# EncoderPCB_V1_0.net
KiCad netlist of a schematic drawn in EAGLE
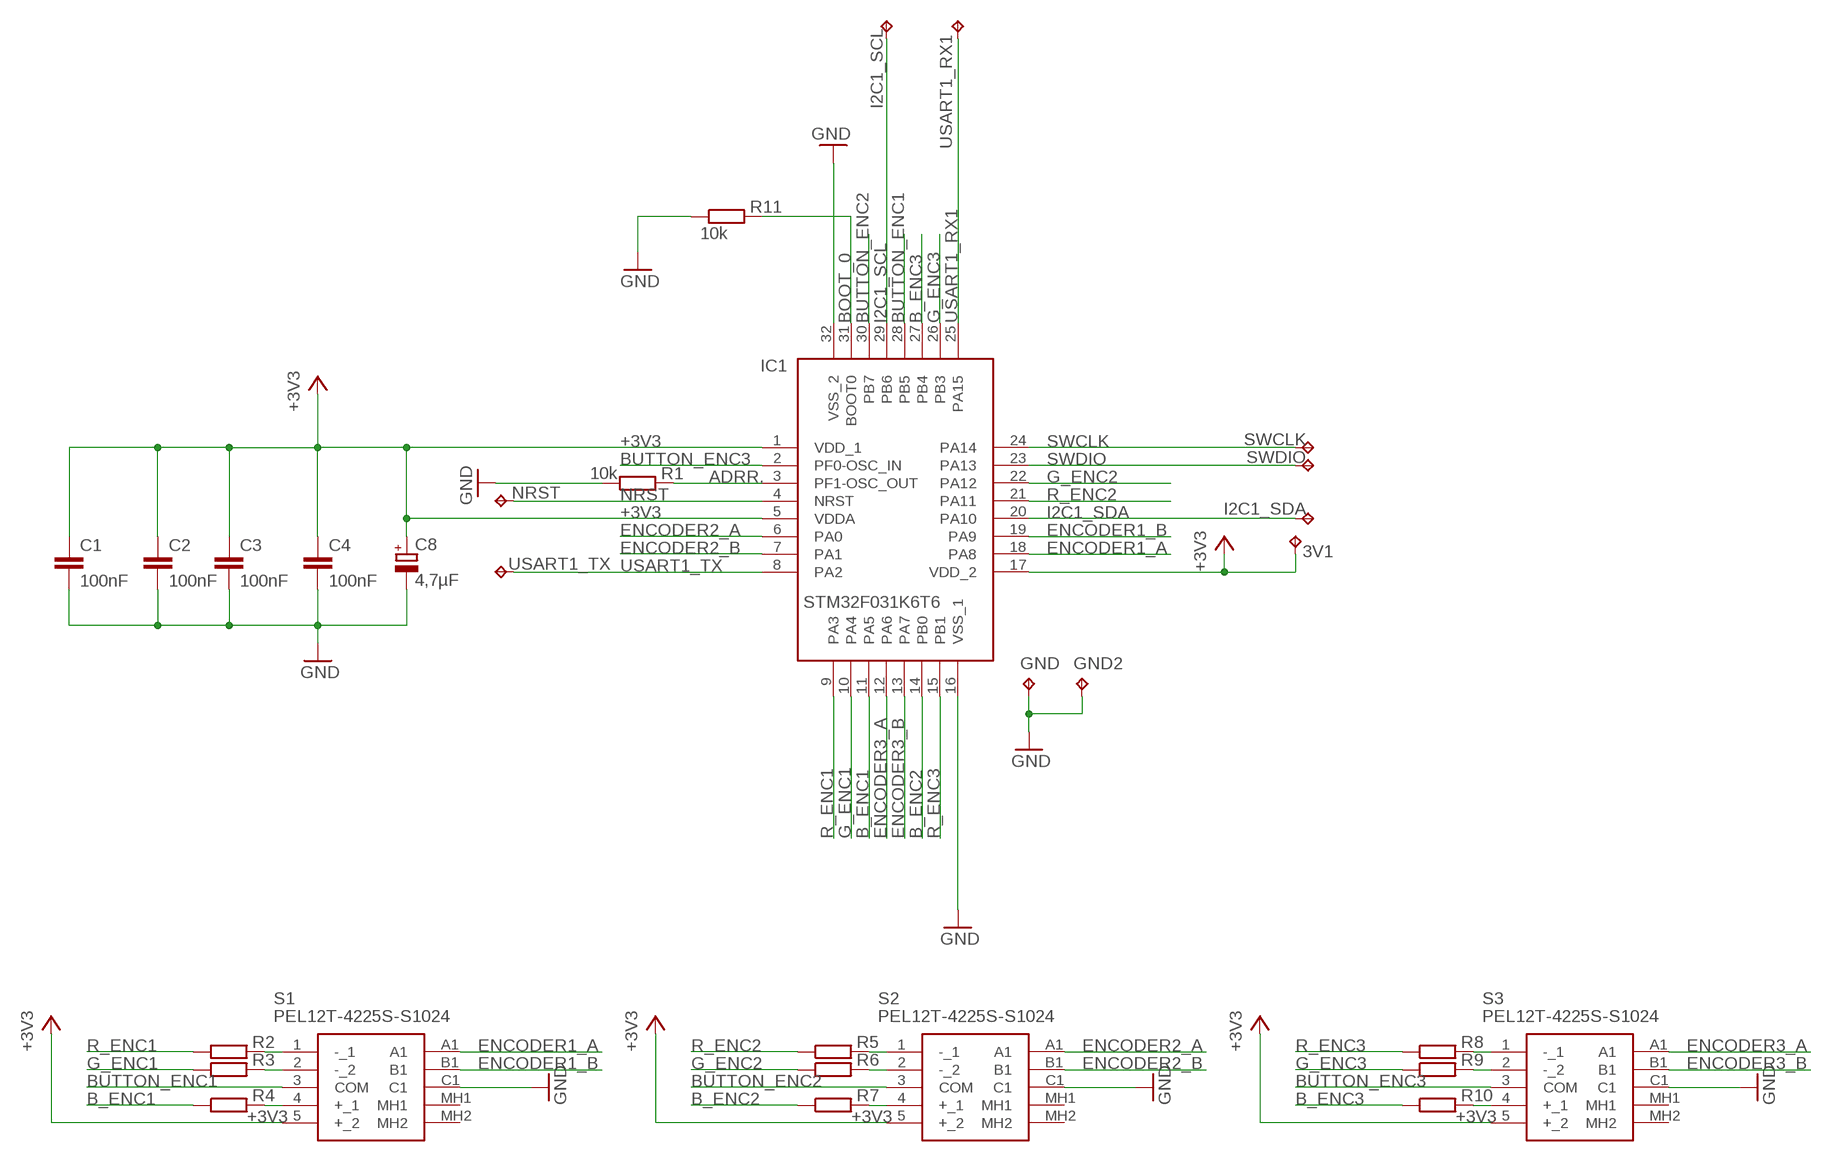
[diagram p0: schematic, sheet 1]

(export (version "E")
  (design (tool "Eeschema 10.0.6"))
  (components
    (comp (ref "3V1")
      (value "TPTHT")
      (footprint "eagle-import:THT_PIN")
      (libsource (lib "eagle-import") (part "TPTHT"))
    )
    (comp (ref "C1")
      (value "100nF")
      (footprint "eagle-import:C0603")
      (libsource (lib "eagle-import") (part "CAPACITOR{dblquote}"))
    )
    (comp (ref "C2")
      (value "100nF")
      (footprint "eagle-import:C0603")
      (libsource (lib "eagle-import") (part "CAPACITOR{dblquote}"))
    )
    (comp (ref "C3")
      (value "100nF")
      (footprint "eagle-import:C0603")
      (libsource (lib "eagle-import") (part "CAPACITOR{dblquote}"))
    )
    (comp (ref "C4")
      (value "100nF")
      (footprint "eagle-import:C0603")
      (libsource (lib "eagle-import") (part "CAPACITOR{dblquote}"))
    )
    (comp (ref "C8")
      (value "4,7µF")
      (footprint "eagle-import:153CLV-0605")
      (libsource (lib "eagle-import") (part "SMD_ELCTROLYTIC"))
    )
    (comp (ref "GND")
      (value "TPTHT")
      (footprint "eagle-import:THT_PIN")
      (libsource (lib "eagle-import") (part "TPTHT"))
    )
    (comp (ref "GND2")
      (value "TPTHT")
      (footprint "eagle-import:THT_PIN")
      (libsource (lib "eagle-import") (part "TPTHT"))
    )
    (comp (ref "I2C1_SCL")
      (value "TPTHT")
      (footprint "eagle-import:THT_PIN")
      (libsource (lib "eagle-import") (part "TPTHT"))
    )
    (comp (ref "I2C1_SDA")
      (value "TPTHT")
      (footprint "eagle-import:THT_PIN")
      (libsource (lib "eagle-import") (part "TPTHT"))
    )
    (comp (ref "IC1")
      (value "STM32F031K6T6")
      (footprint "eagle-import:QFP80P900X900X160-32N")
      (fields (field (name "MOUSER_PART_NUMBER") "511-STM32F031K6T6"))
      (libsource (lib "eagle-import") (part "STM32F031K6T6"))
    )
    (comp (ref "NRST")
      (value "TPTHT")
      (footprint "eagle-import:THT_PIN")
      (libsource (lib "eagle-import") (part "TPTHT"))
    )
    (comp (ref "R1")
      (value "10k")
      (footprint "eagle-import:R0805")
      (libsource (lib "eagle-import") (part "RESISTOR{dblquote}"))
    )
    (comp (ref "R2")
      (value "RESISTOR\"")
      (footprint "eagle-import:R0805")
      (libsource (lib "eagle-import") (part "RESISTOR{dblquote}"))
    )
    (comp (ref "R3")
      (value "RESISTOR\"")
      (footprint "eagle-import:R0805")
      (libsource (lib "eagle-import") (part "RESISTOR{dblquote}"))
    )
    (comp (ref "R4")
      (value "RESISTOR\"")
      (footprint "eagle-import:R0805")
      (libsource (lib "eagle-import") (part "RESISTOR{dblquote}"))
    )
    (comp (ref "R5")
      (value "RESISTOR\"")
      (footprint "eagle-import:R0805")
      (libsource (lib "eagle-import") (part "RESISTOR{dblquote}"))
    )
    (comp (ref "R6")
      (value "RESISTOR\"")
      (footprint "eagle-import:R0805")
      (libsource (lib "eagle-import") (part "RESISTOR{dblquote}"))
    )
    (comp (ref "R7")
      (value "RESISTOR\"")
      (footprint "eagle-import:R0805")
      (libsource (lib "eagle-import") (part "RESISTOR{dblquote}"))
    )
    (comp (ref "R8")
      (value "RESISTOR\"")
      (footprint "eagle-import:R0805")
      (libsource (lib "eagle-import") (part "RESISTOR{dblquote}"))
    )
    (comp (ref "R9")
      (value "RESISTOR\"")
      (footprint "eagle-import:R0805")
      (libsource (lib "eagle-import") (part "RESISTOR{dblquote}"))
    )
    (comp (ref "R10")
      (value "RESISTOR\"")
      (footprint "eagle-import:R0805")
      (libsource (lib "eagle-import") (part "RESISTOR{dblquote}"))
    )
    (comp (ref "R11")
      (value "10k")
      (footprint "eagle-import:R0805")
      (libsource (lib "eagle-import") (part "RESISTOR{dblquote}"))
    )
    (comp (ref "S1")
      (value "PEL12T-4225S-S1024")
      (footprint "eagle-import:PEL12T4225SS1024")
      (fields (field (name "MOUSER_PART_NUMBER") "652-PEL12T4225SS1024"))
      (libsource (lib "eagle-import") (part "PEL12T-4225S-S1024"))
    )
    (comp (ref "S2")
      (value "PEL12T-4225S-S1024")
      (footprint "eagle-import:PEL12T4225SS1024")
      (fields (field (name "MOUSER_PART_NUMBER") "652-PEL12T4225SS1024"))
      (libsource (lib "eagle-import") (part "PEL12T-4225S-S1024"))
    )
    (comp (ref "S3")
      (value "PEL12T-4225S-S1024")
      (footprint "eagle-import:PEL12T4225SS1024")
      (fields (field (name "MOUSER_PART_NUMBER") "652-PEL12T4225SS1024"))
      (libsource (lib "eagle-import") (part "PEL12T-4225S-S1024"))
    )
    (comp (ref "SWCLK")
      (value "TPTHT")
      (footprint "eagle-import:THT_PIN")
      (libsource (lib "eagle-import") (part "TPTHT"))
    )
    (comp (ref "SWDIO")
      (value "TPTHT")
      (footprint "eagle-import:THT_PIN")
      (libsource (lib "eagle-import") (part "TPTHT"))
    )
    (comp (ref "USART1_RX1")
      (value "TPTHT")
      (footprint "eagle-import:THT_PIN")
      (libsource (lib "eagle-import") (part "TPTHT"))
    )
    (comp (ref "USART1_TX")
      (value "TPTHT")
      (footprint "eagle-import:THT_PIN")
      (libsource (lib "eagle-import") (part "TPTHT"))
    )
  )
  (nets
    (net (code "1") (name "+3V3") (class "Default")
      (node (ref "3V1") (pin "P$1") (pinfunction "TP_P$1") (pintype "input"))
      (node (ref "C1") (pin "1") (pinfunction "1_1") (pintype "passive"))
      (node (ref "C2") (pin "1") (pinfunction "1_1") (pintype "passive"))
      (node (ref "C3") (pin "1") (pinfunction "1_1") (pintype "passive"))
      (node (ref "C4") (pin "1") (pinfunction "1_1") (pintype "passive"))
      (node (ref "C8") (pin "+") (pinfunction "+_+") (pintype "passive"))
      (node (ref "IC1") (pin "1") (pinfunction "VDD_1_1") (pintype "bidirectional"))
      (node (ref "IC1") (pin "17") (pinfunction "VDD_2_17") (pintype "bidirectional"))
      (node (ref "IC1") (pin "5") (pinfunction "VDDA_5") (pintype "bidirectional"))
      (node (ref "S1") (pin "5") (pinfunction "+_2_5") (pintype "bidirectional"))
      (node (ref "S2") (pin "5") (pinfunction "+_2_5") (pintype "bidirectional"))
      (node (ref "S3") (pin "5") (pinfunction "+_2_5") (pintype "bidirectional"))
    )
    (net (code "2") (name "/ADRR.") (class "Default")
      (node (ref "IC1") (pin "3") (pinfunction "PF1-OSC_OUT_3") (pintype "bidirectional"))
      (node (ref "R1") (pin "2") (pinfunction "2_2") (pintype "passive"))
    )
    (net (code "3") (name "/BOOT_0") (class "Default")
      (node (ref "IC1") (pin "31") (pinfunction "BOOT0_31") (pintype "bidirectional"))
      (node (ref "R11") (pin "2") (pinfunction "2_2") (pintype "passive"))
    )
    (net (code "4") (name "/BUTTON_ENC1") (class "Default")
      (node (ref "IC1") (pin "28") (pinfunction "PB5_28") (pintype "bidirectional"))
      (node (ref "S1") (pin "3") (pinfunction "COM_3") (pintype "bidirectional"))
    )
    (net (code "5") (name "/BUTTON_ENC2") (class "Default")
      (node (ref "IC1") (pin "30") (pinfunction "PB7_30") (pintype "bidirectional"))
      (node (ref "S2") (pin "3") (pinfunction "COM_3") (pintype "bidirectional"))
    )
    (net (code "6") (name "/BUTTON_ENC3") (class "Default")
      (node (ref "IC1") (pin "2") (pinfunction "PF0-OSC_IN_2") (pintype "bidirectional"))
      (node (ref "S3") (pin "3") (pinfunction "COM_3") (pintype "bidirectional"))
    )
    (net (code "7") (name "/B_ENC1") (class "Default")
      (node (ref "IC1") (pin "11") (pinfunction "PA5_11") (pintype "bidirectional"))
      (node (ref "R4") (pin "1") (pinfunction "1_1") (pintype "passive"))
    )
    (net (code "8") (name "/B_ENC2") (class "Default")
      (node (ref "IC1") (pin "14") (pinfunction "PB0_14") (pintype "bidirectional"))
      (node (ref "R7") (pin "1") (pinfunction "1_1") (pintype "passive"))
    )
    (net (code "9") (name "/B_ENC3") (class "Default")
      (node (ref "IC1") (pin "27") (pinfunction "PB4_27") (pintype "bidirectional"))
      (node (ref "R10") (pin "1") (pinfunction "1_1") (pintype "passive"))
    )
    (net (code "10") (name "/ENCODER1_A") (class "Default")
      (node (ref "IC1") (pin "18") (pinfunction "PA8_18") (pintype "bidirectional"))
      (node (ref "S1") (pin "A1") (pinfunction "A1_A1") (pintype "bidirectional"))
    )
    (net (code "11") (name "/ENCODER1_B") (class "Default")
      (node (ref "IC1") (pin "19") (pinfunction "PA9_19") (pintype "bidirectional"))
      (node (ref "S1") (pin "B1") (pinfunction "B1_B1") (pintype "bidirectional"))
    )
    (net (code "12") (name "/ENCODER2_A") (class "Default")
      (node (ref "IC1") (pin "6") (pinfunction "PA0_6") (pintype "bidirectional"))
      (node (ref "S2") (pin "A1") (pinfunction "A1_A1") (pintype "bidirectional"))
    )
    (net (code "13") (name "/ENCODER2_B") (class "Default")
      (node (ref "IC1") (pin "7") (pinfunction "PA1_7") (pintype "bidirectional"))
      (node (ref "S2") (pin "B1") (pinfunction "B1_B1") (pintype "bidirectional"))
    )
    (net (code "14") (name "/ENCODER3_A") (class "Default")
      (node (ref "IC1") (pin "12") (pinfunction "PA6_12") (pintype "bidirectional"))
      (node (ref "S3") (pin "A1") (pinfunction "A1_A1") (pintype "bidirectional"))
    )
    (net (code "15") (name "/ENCODER3_B") (class "Default")
      (node (ref "IC1") (pin "13") (pinfunction "PA7_13") (pintype "bidirectional"))
      (node (ref "S3") (pin "B1") (pinfunction "B1_B1") (pintype "bidirectional"))
    )
    (net (code "16") (name "/G_ENC1") (class "Default")
      (node (ref "IC1") (pin "10") (pinfunction "PA4_10") (pintype "bidirectional"))
      (node (ref "R3") (pin "1") (pinfunction "1_1") (pintype "passive"))
    )
    (net (code "17") (name "/G_ENC2") (class "Default")
      (node (ref "IC1") (pin "22") (pinfunction "PA12_22") (pintype "bidirectional"))
      (node (ref "R6") (pin "1") (pinfunction "1_1") (pintype "passive"))
    )
    (net (code "18") (name "/G_ENC3") (class "Default")
      (node (ref "IC1") (pin "26") (pinfunction "PB3_26") (pintype "bidirectional"))
      (node (ref "R9") (pin "1") (pinfunction "1_1") (pintype "passive"))
    )
    (net (code "19") (name "/I2C1_SCL") (class "Default")
      (node (ref "I2C1_SCL") (pin "P$1") (pinfunction "TP_P$1") (pintype "input"))
      (node (ref "IC1") (pin "29") (pinfunction "PB6_29") (pintype "bidirectional"))
    )
    (net (code "20") (name "/I2C1_SDA") (class "Default")
      (node (ref "I2C1_SDA") (pin "P$1") (pinfunction "TP_P$1") (pintype "input"))
      (node (ref "IC1") (pin "20") (pinfunction "PA10_20") (pintype "bidirectional"))
    )
    (net (code "21") (name "/NRST") (class "Default")
      (node (ref "IC1") (pin "4") (pinfunction "NRST_4") (pintype "bidirectional"))
      (node (ref "NRST") (pin "P$1") (pinfunction "TP_P$1") (pintype "input"))
    )
    (net (code "22") (name "/R_ENC1") (class "Default")
      (node (ref "IC1") (pin "9") (pinfunction "PA3_9") (pintype "bidirectional"))
      (node (ref "R2") (pin "1") (pinfunction "1_1") (pintype "passive"))
    )
    (net (code "23") (name "/R_ENC2") (class "Default")
      (node (ref "IC1") (pin "21") (pinfunction "PA11_21") (pintype "bidirectional"))
      (node (ref "R5") (pin "1") (pinfunction "1_1") (pintype "passive"))
    )
    (net (code "24") (name "/R_ENC3") (class "Default")
      (node (ref "IC1") (pin "15") (pinfunction "PB1_15") (pintype "bidirectional"))
      (node (ref "R8") (pin "1") (pinfunction "1_1") (pintype "passive"))
    )
    (net (code "25") (name "/SWCLK") (class "Default")
      (node (ref "IC1") (pin "24") (pinfunction "PA14_24") (pintype "bidirectional"))
      (node (ref "SWCLK") (pin "P$1") (pinfunction "TP_P$1") (pintype "input"))
    )
    (net (code "26") (name "/SWDIO") (class "Default")
      (node (ref "IC1") (pin "23") (pinfunction "PA13_23") (pintype "bidirectional"))
      (node (ref "SWDIO") (pin "P$1") (pinfunction "TP_P$1") (pintype "input"))
    )
    (net (code "27") (name "/USART1_RX1") (class "Default")
      (node (ref "IC1") (pin "25") (pinfunction "PA15_25") (pintype "bidirectional"))
      (node (ref "USART1_RX1") (pin "P$1") (pinfunction "TP_P$1") (pintype "input"))
    )
    (net (code "28") (name "/USART1_TX") (class "Default")
      (node (ref "IC1") (pin "8") (pinfunction "PA2_8") (pintype "bidirectional"))
      (node (ref "USART1_TX") (pin "P$1") (pinfunction "TP_P$1") (pintype "input"))
    )
    (net (code "29") (name "GND") (class "Default")
      (node (ref "C1") (pin "2") (pinfunction "2_2") (pintype "passive"))
      (node (ref "C2") (pin "2") (pinfunction "2_2") (pintype "passive"))
      (node (ref "C3") (pin "2") (pinfunction "2_2") (pintype "passive"))
      (node (ref "C4") (pin "2") (pinfunction "2_2") (pintype "passive"))
      (node (ref "C8") (pin "-") (pinfunction "-_-") (pintype "passive"))
      (node (ref "GND") (pin "P$1") (pinfunction "TP_P$1") (pintype "input"))
      (node (ref "GND2") (pin "P$1") (pinfunction "TP_P$1") (pintype "input"))
      (node (ref "IC1") (pin "16") (pinfunction "VSS_1_16") (pintype "bidirectional"))
      (node (ref "IC1") (pin "32") (pinfunction "VSS_2_32") (pintype "bidirectional"))
      (node (ref "R1") (pin "1") (pinfunction "1_1") (pintype "passive"))
      (node (ref "R11") (pin "1") (pinfunction "1_1") (pintype "passive"))
      (node (ref "S1") (pin "C1") (pinfunction "C1_C1") (pintype "bidirectional"))
      (node (ref "S2") (pin "C1") (pinfunction "C1_C1") (pintype "bidirectional"))
      (node (ref "S3") (pin "C1") (pinfunction "C1_C1") (pintype "bidirectional"))
    )
    (net (code "30") (name "Net-(S1-+_1)") (class "Default")
      (node (ref "R4") (pin "2") (pinfunction "2_2") (pintype "passive"))
      (node (ref "S1") (pin "4") (pinfunction "+_1_4") (pintype "bidirectional"))
    )
    (net (code "31") (name "Net-(S1--_1)") (class "Default")
      (node (ref "R2") (pin "2") (pinfunction "2_2") (pintype "passive"))
      (node (ref "S1") (pin "1") (pinfunction "-_1_1") (pintype "bidirectional"))
    )
    (net (code "32") (name "Net-(S1--_2)") (class "Default")
      (node (ref "R3") (pin "2") (pinfunction "2_2") (pintype "passive"))
      (node (ref "S1") (pin "2") (pinfunction "-_2_2") (pintype "bidirectional"))
    )
    (net (code "33") (name "Net-(S2-+_1)") (class "Default")
      (node (ref "R7") (pin "2") (pinfunction "2_2") (pintype "passive"))
      (node (ref "S2") (pin "4") (pinfunction "+_1_4") (pintype "bidirectional"))
    )
    (net (code "34") (name "Net-(S2--_1)") (class "Default")
      (node (ref "R5") (pin "2") (pinfunction "2_2") (pintype "passive"))
      (node (ref "S2") (pin "1") (pinfunction "-_1_1") (pintype "bidirectional"))
    )
    (net (code "35") (name "Net-(S2--_2)") (class "Default")
      (node (ref "R6") (pin "2") (pinfunction "2_2") (pintype "passive"))
      (node (ref "S2") (pin "2") (pinfunction "-_2_2") (pintype "bidirectional"))
    )
    (net (code "36") (name "Net-(S3-+_1)") (class "Default")
      (node (ref "R10") (pin "2") (pinfunction "2_2") (pintype "passive"))
      (node (ref "S3") (pin "4") (pinfunction "+_1_4") (pintype "bidirectional"))
    )
    (net (code "37") (name "Net-(S3--_1)") (class "Default")
      (node (ref "R8") (pin "2") (pinfunction "2_2") (pintype "passive"))
      (node (ref "S3") (pin "1") (pinfunction "-_1_1") (pintype "bidirectional"))
    )
    (net (code "38") (name "Net-(S3--_2)") (class "Default")
      (node (ref "R9") (pin "2") (pinfunction "2_2") (pintype "passive"))
      (node (ref "S3") (pin "2") (pinfunction "-_2_2") (pintype "bidirectional"))
    )
    (net (code "39") (name "unconnected-(S1-PadMH1)") (class "Default")
      (node (ref "S1") (pin "MH1") (pinfunction "MH1_MH1") (pintype "bidirectional"))
    )
    (net (code "40") (name "unconnected-(S1-PadMH2)") (class "Default")
      (node (ref "S1") (pin "MH2") (pinfunction "MH2_MH2") (pintype "bidirectional"))
    )
    (net (code "41") (name "unconnected-(S2-PadMH1)") (class "Default")
      (node (ref "S2") (pin "MH1") (pinfunction "MH1_MH1") (pintype "bidirectional"))
    )
    (net (code "42") (name "unconnected-(S2-PadMH2)") (class "Default")
      (node (ref "S2") (pin "MH2") (pinfunction "MH2_MH2") (pintype "bidirectional"))
    )
    (net (code "43") (name "unconnected-(S3-PadMH1)") (class "Default")
      (node (ref "S3") (pin "MH1") (pinfunction "MH1_MH1") (pintype "bidirectional"))
    )
    (net (code "44") (name "unconnected-(S3-PadMH2)") (class "Default")
      (node (ref "S3") (pin "MH2") (pinfunction "MH2_MH2") (pintype "bidirectional"))
    )
  )
)
